# 1V1_REG.net
KiCad netlist of a schematic drawn in Altium Designer
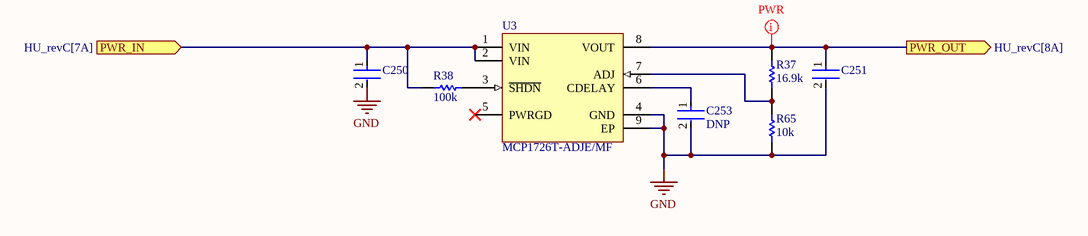
[diagram p0: 1V1_REG.SchDoc]

(export (version "E")
  (design (tool "Eeschema 10.0.6"))
  (components
    (comp (ref "C250")
      (value "C0805C475J4RACAUTO")
      (footprint "FP-C0805C475J4RACAUTO-MFG")
      (description "C0805C475J4RACAUTO Cap Ceramic 4.7uF 16V X7R 5% Pad SMD 0805 125C Automotive T/R")
      (fields (field (name "TOLERANCE") "5%"))
      (libsource (lib "Altium Content Vault") (part "b4654b650e69147ec39a6b967a45e02"))
    )
    (comp (ref "C251")
      (value "GRM21BR61E226ME44L")
      (footprint "FP-GRM21B-0_2-e0_2_0_7-IPC_B")
      (description "Chip Multilayer Ceramic Capacitors for General Purpose, 0805, 22uF, X5R, 15%, 20%, 25V")
      (fields (field (name "TOLERANCE") "20%") (field (name "VOLTAGE") "25V"))
      (libsource (lib "Altium Content Vault") (part "b4654b650e69147ec39a6b967a45e02"))
    )
    (comp (ref "C253")
      (value "DNP")
      (footprint "FP-0402-L_1_0_0_05-W_0_5-IPC_A")
      (description "LARGE PADS, 0402 CAP, CHANGE COMMENT TO MATCH REAL P/N")
      (libsource (lib "Space Concordia") (part "b4654b650e69147ec39a6b967a45e02"))
    )
    (comp (ref "R37")
      (value "16.9k")
      (footprint "R0603B")
      (description "Resistor")
      (libsource (lib "Space Concordia") (part "Resistor"))
    )
    (comp (ref "R38")
      (value "100k")
      (footprint "R0603B")
      (description "Resistor")
      (libsource (lib "Space Concordia") (part "Resistor"))
    )
    (comp (ref "R65")
      (value "10k")
      (footprint "R0603B")
      (description "Resistor")
      (libsource (lib "Space Concordia") (part "Resistor"))
    )
    (comp (ref "U3")
      (value "MCP1726T-ADJE/MF")
      (footprint "DFN-MF8")
      (libsource (lib "Altium Content Vault") (part "PM-LINEREG-MCP1726-IL9A"))
    )
  )
  (nets
    (net (code "1") (name "/PWR_IN") (class "Default")
      (node (ref "C250") (pin "1") (pinfunction "1_1") (pintype "passive"))
      (node (ref "R38") (pin "1") (pinfunction "1_1") (pintype "passive"))
      (node (ref "U3") (pin "1") (pinfunction "VIN_1") (pintype "power_in"))
      (node (ref "U3") (pin "2") (pinfunction "VIN_2") (pintype "power_in"))
    )
    (net (code "2") (name "/PWR_OUT") (class "Default")
      (node (ref "C251") (pin "1") (pinfunction "1_1") (pintype "passive"))
      (node (ref "R37") (pin "2") (pinfunction "2_2") (pintype "passive"))
      (node (ref "U3") (pin "8") (pinfunction "VOUT_8") (pintype "power_in"))
    )
    (net (code "3") (name "GND") (class "Default")
      (node (ref "C250") (pin "2") (pinfunction "2_2") (pintype "passive"))
      (node (ref "C251") (pin "2") (pinfunction "2_2") (pintype "passive"))
      (node (ref "C253") (pin "2") (pinfunction "2_2") (pintype "passive"))
      (node (ref "R65") (pin "1") (pinfunction "1_1") (pintype "passive"))
      (node (ref "U3") (pin "4") (pinfunction "GND_4") (pintype "power_in"))
      (node (ref "U3") (pin "9") (pinfunction "EP_9") (pintype "power_in"))
    )
    (net (code "4") (name "Net-(U3-ADJ)") (class "Default")
      (node (ref "R37") (pin "1") (pinfunction "1_1") (pintype "passive"))
      (node (ref "R65") (pin "2") (pinfunction "2_2") (pintype "passive"))
      (node (ref "U3") (pin "7") (pinfunction "ADJ_7") (pintype "input"))
    )
    (net (code "5") (name "Net-(U3-CDELAY)") (class "Default")
      (node (ref "C253") (pin "1") (pinfunction "1_1") (pintype "passive"))
      (node (ref "U3") (pin "6") (pinfunction "CDELAY_6") (pintype "passive"))
    )
    (net (code "6") (name "Net-(U3-~{SHDN})") (class "Default")
      (node (ref "R38") (pin "2") (pinfunction "2_2") (pintype "passive"))
      (node (ref "U3") (pin "3") (pinfunction "~{SHDN}_3") (pintype "input"))
    )
    (net (code "7") (name "unconnected-(U3-PWRGD-Pad5)") (class "Default")
      (node (ref "U3") (pin "5") (pinfunction "PWRGD_5") (pintype "power_in+no_connect"))
    )
  )
)
